# PropellerClock.net
KiCad netlist of a schematic drawn in EAGLE
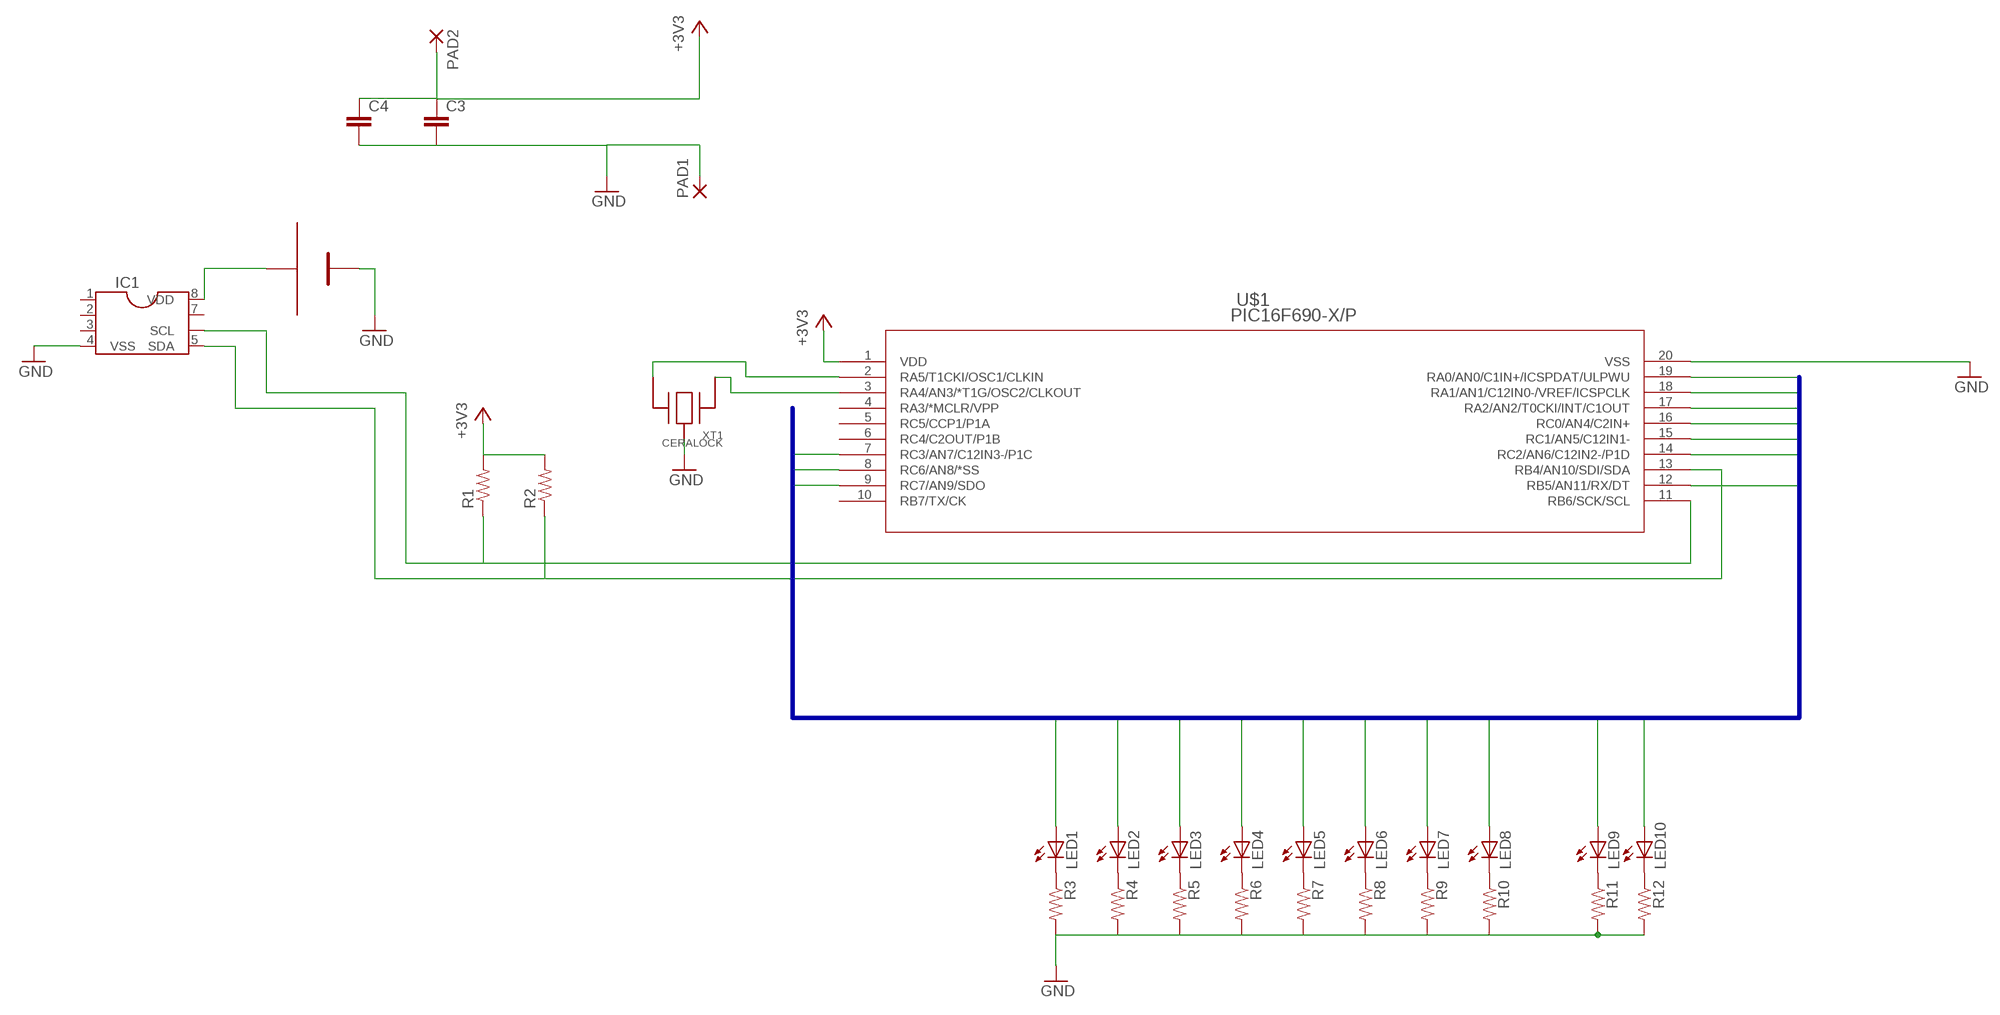
[diagram p0: schematic, sheet 1]

(export (version "E")
  (design (tool "Eeschema 10.0.6"))
  (components
    (comp (ref "C3")
      (value "C-EUC2012")
      (footprint "eagle-import:C2012")
      (libsource (lib "eagle-import") (part "C-EUC2012"))
    )
    (comp (ref "C4")
      (value "C-EUC2012")
      (footprint "eagle-import:C2012")
      (libsource (lib "eagle-import") (part "C-EUC2012"))
    )
    (comp (ref "IC1")
      (value "DIL8S")
      (footprint "eagle-import:SOCKET-08")
      (libsource (lib "eagle-import") (part "DIL8S"))
    )
    (comp (ref "LED1")
      (value "LED3MM")
      (footprint "eagle-import:LED3MM")
      (libsource (lib "eagle-import") (part "LED3MM"))
    )
    (comp (ref "LED2")
      (value "LED3MM")
      (footprint "eagle-import:LED3MM")
      (libsource (lib "eagle-import") (part "LED3MM"))
    )
    (comp (ref "LED3")
      (value "LED3MM")
      (footprint "eagle-import:LED3MM")
      (libsource (lib "eagle-import") (part "LED3MM"))
    )
    (comp (ref "LED4")
      (value "LED3MM")
      (footprint "eagle-import:LED3MM")
      (libsource (lib "eagle-import") (part "LED3MM"))
    )
    (comp (ref "LED5")
      (value "LED3MM")
      (footprint "eagle-import:LED3MM")
      (libsource (lib "eagle-import") (part "LED3MM"))
    )
    (comp (ref "LED6")
      (value "LED3MM")
      (footprint "eagle-import:LED3MM")
      (libsource (lib "eagle-import") (part "LED3MM"))
    )
    (comp (ref "LED7")
      (value "LED3MM")
      (footprint "eagle-import:LED3MM")
      (libsource (lib "eagle-import") (part "LED3MM"))
    )
    (comp (ref "LED8")
      (value "LED3MM")
      (footprint "eagle-import:LED3MM")
      (libsource (lib "eagle-import") (part "LED3MM"))
    )
    (comp (ref "LED9")
      (value "LED3MM")
      (footprint "eagle-import:LED3MM")
      (libsource (lib "eagle-import") (part "LED3MM"))
    )
    (comp (ref "LED10")
      (value "LED3MM")
      (footprint "eagle-import:LED3MM")
      (libsource (lib "eagle-import") (part "LED3MM"))
    )
    (comp (ref "PAD1")
      (value "2,54/1,0")
      (footprint "eagle-import:2,54_1,0")
      (libsource (lib "eagle-import") (part "2,54/1,0"))
    )
    (comp (ref "PAD2")
      (value "2,54/1,0")
      (footprint "eagle-import:2,54_1,0")
      (libsource (lib "eagle-import") (part "2,54/1,0"))
    )
    (comp (ref "R1")
      (value "R-US_0204/7")
      (footprint "eagle-import:0204_7")
      (libsource (lib "eagle-import") (part "R-US_0204/7"))
    )
    (comp (ref "R2")
      (value "R-US_0204/7")
      (footprint "eagle-import:0204_7")
      (libsource (lib "eagle-import") (part "R-US_0204/7"))
    )
    (comp (ref "R3")
      (value "R-US_0207/7")
      (footprint "eagle-import:0207_7")
      (libsource (lib "eagle-import") (part "R-US_0207/7"))
    )
    (comp (ref "R4")
      (value "R-US_0207/7")
      (footprint "eagle-import:0207_7")
      (libsource (lib "eagle-import") (part "R-US_0207/7"))
    )
    (comp (ref "R5")
      (value "R-US_0207/7")
      (footprint "eagle-import:0207_7")
      (libsource (lib "eagle-import") (part "R-US_0207/7"))
    )
    (comp (ref "R6")
      (value "R-US_0207/7")
      (footprint "eagle-import:0207_7")
      (libsource (lib "eagle-import") (part "R-US_0207/7"))
    )
    (comp (ref "R7")
      (value "R-US_0207/7")
      (footprint "eagle-import:0207_7")
      (libsource (lib "eagle-import") (part "R-US_0207/7"))
    )
    (comp (ref "R8")
      (value "R-US_0207/7")
      (footprint "eagle-import:0207_7")
      (libsource (lib "eagle-import") (part "R-US_0207/7"))
    )
    (comp (ref "R9")
      (value "R-US_0207/7")
      (footprint "eagle-import:0207_7")
      (libsource (lib "eagle-import") (part "R-US_0207/7"))
    )
    (comp (ref "R10")
      (value "R-US_0207/7")
      (footprint "eagle-import:0207_7")
      (libsource (lib "eagle-import") (part "R-US_0207/7"))
    )
    (comp (ref "R11")
      (value "R-US_0207/7")
      (footprint "eagle-import:0207_7")
      (libsource (lib "eagle-import") (part "R-US_0207/7"))
    )
    (comp (ref "R12")
      (value "R-US_0207/7")
      (footprint "eagle-import:0207_7")
      (libsource (lib "eagle-import") (part "R-US_0207/7"))
    )
    (comp (ref "U$1")
      (value "PIC16F690-X/P")
      (footprint "eagle-import:PDIP20_300MC")
      (libsource (lib "eagle-import") (part "PIC16F690-X/P"))
    )
    (comp (ref "U$2")
      (value "CR2032-HOLDER2")
      (footprint "eagle-import:CR2032-HOLDER2")
      (libsource (lib "eagle-import") (part "CR2032-HOLDER2"))
    )
    (comp (ref "XT1")
      (value "CERALOCK")
      (footprint "eagle-import:CERALOCK")
      (libsource (lib "eagle-import") (part "CERALOCK"))
    )
  )
  (nets
    (net (code "1") (name "+3V3") (class "Default")
      (node (ref "C3") (pin "1") (pinfunction "1_1") (pintype "passive"))
      (node (ref "C4") (pin "1") (pinfunction "1_1") (pintype "passive"))
      (node (ref "PAD2") (pin "1") (pinfunction "P_1") (pintype "passive"))
      (node (ref "R1") (pin "2") (pinfunction "2_2") (pintype "passive"))
      (node (ref "R2") (pin "2") (pinfunction "2_2") (pintype "passive"))
      (node (ref "U$1") (pin "1") (pinfunction "VDD_1") (pintype "passive"))
    )
    (net (code "2") (name "/LED_BUS1") (class "Default")
      (node (ref "LED1") (pin "A") (pinfunction "A_A") (pintype "passive"))
      (node (ref "U$1") (pin "7") (pinfunction "RC3/AN7/C12IN3-/P1C_7") (pintype "passive"))
    )
    (net (code "3") (name "/LED_BUS2") (class "Default")
      (node (ref "LED2") (pin "A") (pinfunction "A_A") (pintype "passive"))
      (node (ref "U$1") (pin "19") (pinfunction "RA0/AN0/C1IN+/ICSPDAT/ULPWU_19") (pintype "passive"))
    )
    (net (code "4") (name "/LED_BUS3") (class "Default")
      (node (ref "LED3") (pin "A") (pinfunction "A_A") (pintype "passive"))
      (node (ref "U$1") (pin "18") (pinfunction "RA1/AN1/C12IN0-/VREF/ICSPCLK_18") (pintype "passive"))
    )
    (net (code "5") (name "/LED_BUS4") (class "Default")
      (node (ref "LED4") (pin "A") (pinfunction "A_A") (pintype "passive"))
      (node (ref "U$1") (pin "17") (pinfunction "RA2/AN2/T0CKI/INT/C1OUT_17") (pintype "passive"))
    )
    (net (code "6") (name "/LED_BUS5") (class "Default")
      (node (ref "LED5") (pin "A") (pinfunction "A_A") (pintype "passive"))
      (node (ref "U$1") (pin "16") (pinfunction "RC0/AN4/C2IN+_16") (pintype "passive"))
    )
    (net (code "7") (name "/LED_BUS6") (class "Default")
      (node (ref "LED6") (pin "A") (pinfunction "A_A") (pintype "passive"))
      (node (ref "U$1") (pin "15") (pinfunction "RC1/AN5/C12IN1-_15") (pintype "passive"))
    )
    (net (code "8") (name "/LED_BUS7") (class "Default")
      (node (ref "LED7") (pin "A") (pinfunction "A_A") (pintype "passive"))
      (node (ref "U$1") (pin "14") (pinfunction "RC2/AN6/C12IN2-/P1D_14") (pintype "passive"))
    )
    (net (code "9") (name "/LED_BUS8") (class "Default")
      (node (ref "LED8") (pin "A") (pinfunction "A_A") (pintype "passive"))
      (node (ref "U$1") (pin "12") (pinfunction "RB5/AN11/RX/DT_12") (pintype "passive"))
    )
    (net (code "10") (name "/LED_BUS9") (class "Default")
      (node (ref "LED9") (pin "A") (pinfunction "A_A") (pintype "passive"))
      (node (ref "U$1") (pin "8") (pinfunction "RC6/AN8/*SS_8") (pintype "passive"))
    )
    (net (code "11") (name "/LED_BUS10") (class "Default")
      (node (ref "LED10") (pin "A") (pinfunction "A_A") (pintype "passive"))
      (node (ref "U$1") (pin "9") (pinfunction "RC7/AN9/SDO_9") (pintype "passive"))
    )
    (net (code "12") (name "GND") (class "Default")
      (node (ref "C3") (pin "2") (pinfunction "2_2") (pintype "passive"))
      (node (ref "C4") (pin "2") (pinfunction "2_2") (pintype "passive"))
      (node (ref "IC1") (pin "4") (pinfunction "VSS_4") (pintype "passive"))
      (node (ref "PAD1") (pin "1") (pinfunction "P_1") (pintype "passive"))
      (node (ref "R10") (pin "2") (pinfunction "2_2") (pintype "passive"))
      (node (ref "R11") (pin "2") (pinfunction "2_2") (pintype "passive"))
      (node (ref "R12") (pin "2") (pinfunction "2_2") (pintype "passive"))
      (node (ref "R3") (pin "2") (pinfunction "2_2") (pintype "passive"))
      (node (ref "R4") (pin "2") (pinfunction "2_2") (pintype "passive"))
      (node (ref "R5") (pin "2") (pinfunction "2_2") (pintype "passive"))
      (node (ref "R6") (pin "2") (pinfunction "2_2") (pintype "passive"))
      (node (ref "R7") (pin "2") (pinfunction "2_2") (pintype "passive"))
      (node (ref "R8") (pin "2") (pinfunction "2_2") (pintype "passive"))
      (node (ref "R9") (pin "2") (pinfunction "2_2") (pintype "passive"))
      (node (ref "U$1") (pin "20") (pinfunction "VSS_20") (pintype "passive"))
      (node (ref "U$2") (pin "GND") (pinfunction "GND_GND") (pintype "bidirectional"))
      (node (ref "XT1") (pin "P$2") (pinfunction "2_P$2") (pintype "passive"))
    )
    (net (code "13") (name "Net-(IC1-SCL)") (class "Default")
      (node (ref "IC1") (pin "6") (pinfunction "SCL_6") (pintype "passive"))
      (node (ref "R1") (pin "1") (pinfunction "1_1") (pintype "passive"))
      (node (ref "U$1") (pin "11") (pinfunction "RB6/SCK/SCL_11") (pintype "passive"))
    )
    (net (code "14") (name "Net-(IC1-SDA)") (class "Default")
      (node (ref "IC1") (pin "5") (pinfunction "SDA_5") (pintype "passive"))
      (node (ref "R2") (pin "1") (pinfunction "1_1") (pintype "passive"))
      (node (ref "U$1") (pin "13") (pinfunction "RB4/AN10/SDI/SDA_13") (pintype "passive"))
    )
    (net (code "15") (name "Net-(IC1-VDD)") (class "Default")
      (node (ref "IC1") (pin "8") (pinfunction "VDD_8") (pintype "passive"))
      (node (ref "U$2") (pin "+3V") (pinfunction "+3V_+3V") (pintype "bidirectional"))
    )
    (net (code "16") (name "Net-(LED1-C)") (class "Default")
      (node (ref "LED1") (pin "K") (pinfunction "C_K") (pintype "passive"))
      (node (ref "R3") (pin "1") (pinfunction "1_1") (pintype "passive"))
    )
    (net (code "17") (name "Net-(LED2-C)") (class "Default")
      (node (ref "LED2") (pin "K") (pinfunction "C_K") (pintype "passive"))
      (node (ref "R4") (pin "1") (pinfunction "1_1") (pintype "passive"))
    )
    (net (code "18") (name "Net-(LED3-C)") (class "Default")
      (node (ref "LED3") (pin "K") (pinfunction "C_K") (pintype "passive"))
      (node (ref "R5") (pin "1") (pinfunction "1_1") (pintype "passive"))
    )
    (net (code "19") (name "Net-(LED4-C)") (class "Default")
      (node (ref "LED4") (pin "K") (pinfunction "C_K") (pintype "passive"))
      (node (ref "R6") (pin "1") (pinfunction "1_1") (pintype "passive"))
    )
    (net (code "20") (name "Net-(LED5-C)") (class "Default")
      (node (ref "LED5") (pin "K") (pinfunction "C_K") (pintype "passive"))
      (node (ref "R7") (pin "1") (pinfunction "1_1") (pintype "passive"))
    )
    (net (code "21") (name "Net-(LED6-C)") (class "Default")
      (node (ref "LED6") (pin "K") (pinfunction "C_K") (pintype "passive"))
      (node (ref "R8") (pin "1") (pinfunction "1_1") (pintype "passive"))
    )
    (net (code "22") (name "Net-(LED7-C)") (class "Default")
      (node (ref "LED7") (pin "K") (pinfunction "C_K") (pintype "passive"))
      (node (ref "R9") (pin "1") (pinfunction "1_1") (pintype "passive"))
    )
    (net (code "23") (name "Net-(LED8-C)") (class "Default")
      (node (ref "LED8") (pin "K") (pinfunction "C_K") (pintype "passive"))
      (node (ref "R10") (pin "1") (pinfunction "1_1") (pintype "passive"))
    )
    (net (code "24") (name "Net-(LED9-C)") (class "Default")
      (node (ref "LED9") (pin "K") (pinfunction "C_K") (pintype "passive"))
      (node (ref "R11") (pin "1") (pinfunction "1_1") (pintype "passive"))
    )
    (net (code "25") (name "Net-(LED10-C)") (class "Default")
      (node (ref "LED10") (pin "K") (pinfunction "C_K") (pintype "passive"))
      (node (ref "R12") (pin "1") (pinfunction "1_1") (pintype "passive"))
    )
    (net (code "26") (name "Net-(U$1-RA4{slash}AN3{slash}*T1G{slash}OSC2{slash}CLKOUT)") (class "Default")
      (node (ref "U$1") (pin "3") (pinfunction "RA4/AN3/*T1G/OSC2/CLKOUT_3") (pintype "passive"))
      (node (ref "XT1") (pin "P$1") (pinfunction "1_P$1") (pintype "passive"))
    )
    (net (code "27") (name "Net-(U$1-RA5{slash}T1CKI{slash}OSC1{slash}CLKIN)") (class "Default")
      (node (ref "U$1") (pin "2") (pinfunction "RA5/T1CKI/OSC1/CLKIN_2") (pintype "passive"))
      (node (ref "XT1") (pin "P$3") (pinfunction "3_P$3") (pintype "passive"))
    )
    (net (code "28") (name "unconnected-(IC1-CLKOE-Pad1)") (class "Default")
      (node (ref "IC1") (pin "1") (pinfunction "CLKOE_1") (pintype "passive"))
    )
    (net (code "29") (name "unconnected-(IC1-CLKOUT-Pad2)") (class "Default")
      (node (ref "IC1") (pin "2") (pinfunction "CLKOUT_2") (pintype "passive"))
    )
    (net (code "30") (name "unconnected-(IC1-INT-Pad3)") (class "Default")
      (node (ref "IC1") (pin "3") (pinfunction "INT_3") (pintype "passive"))
    )
    (net (code "31") (name "unconnected-(IC1-V.C.-Pad7)") (class "Default")
      (node (ref "IC1") (pin "7") (pinfunction "V.C._7") (pintype "passive"))
    )
    (net (code "32") (name "unconnected-(U$1-RA3{slash}*MCLR{slash}VPP-Pad4)") (class "Default")
      (node (ref "U$1") (pin "4") (pinfunction "RA3/*MCLR/VPP_4") (pintype "passive"))
    )
    (net (code "33") (name "unconnected-(U$1-RB7{slash}TX{slash}CK-Pad10)") (class "Default")
      (node (ref "U$1") (pin "10") (pinfunction "RB7/TX/CK_10") (pintype "passive"))
    )
    (net (code "34") (name "unconnected-(U$1-RC4{slash}C2OUT{slash}P1B-Pad6)") (class "Default")
      (node (ref "U$1") (pin "6") (pinfunction "RC4/C2OUT/P1B_6") (pintype "passive"))
    )
    (net (code "35") (name "unconnected-(U$1-RC5{slash}CCP1{slash}P1A-Pad5)") (class "Default")
      (node (ref "U$1") (pin "5") (pinfunction "RC5/CCP1/P1A_5") (pintype "passive"))
    )
  )
)
